# Side_Sensor.net
KiCad netlist of a schematic drawn in EasyEDA
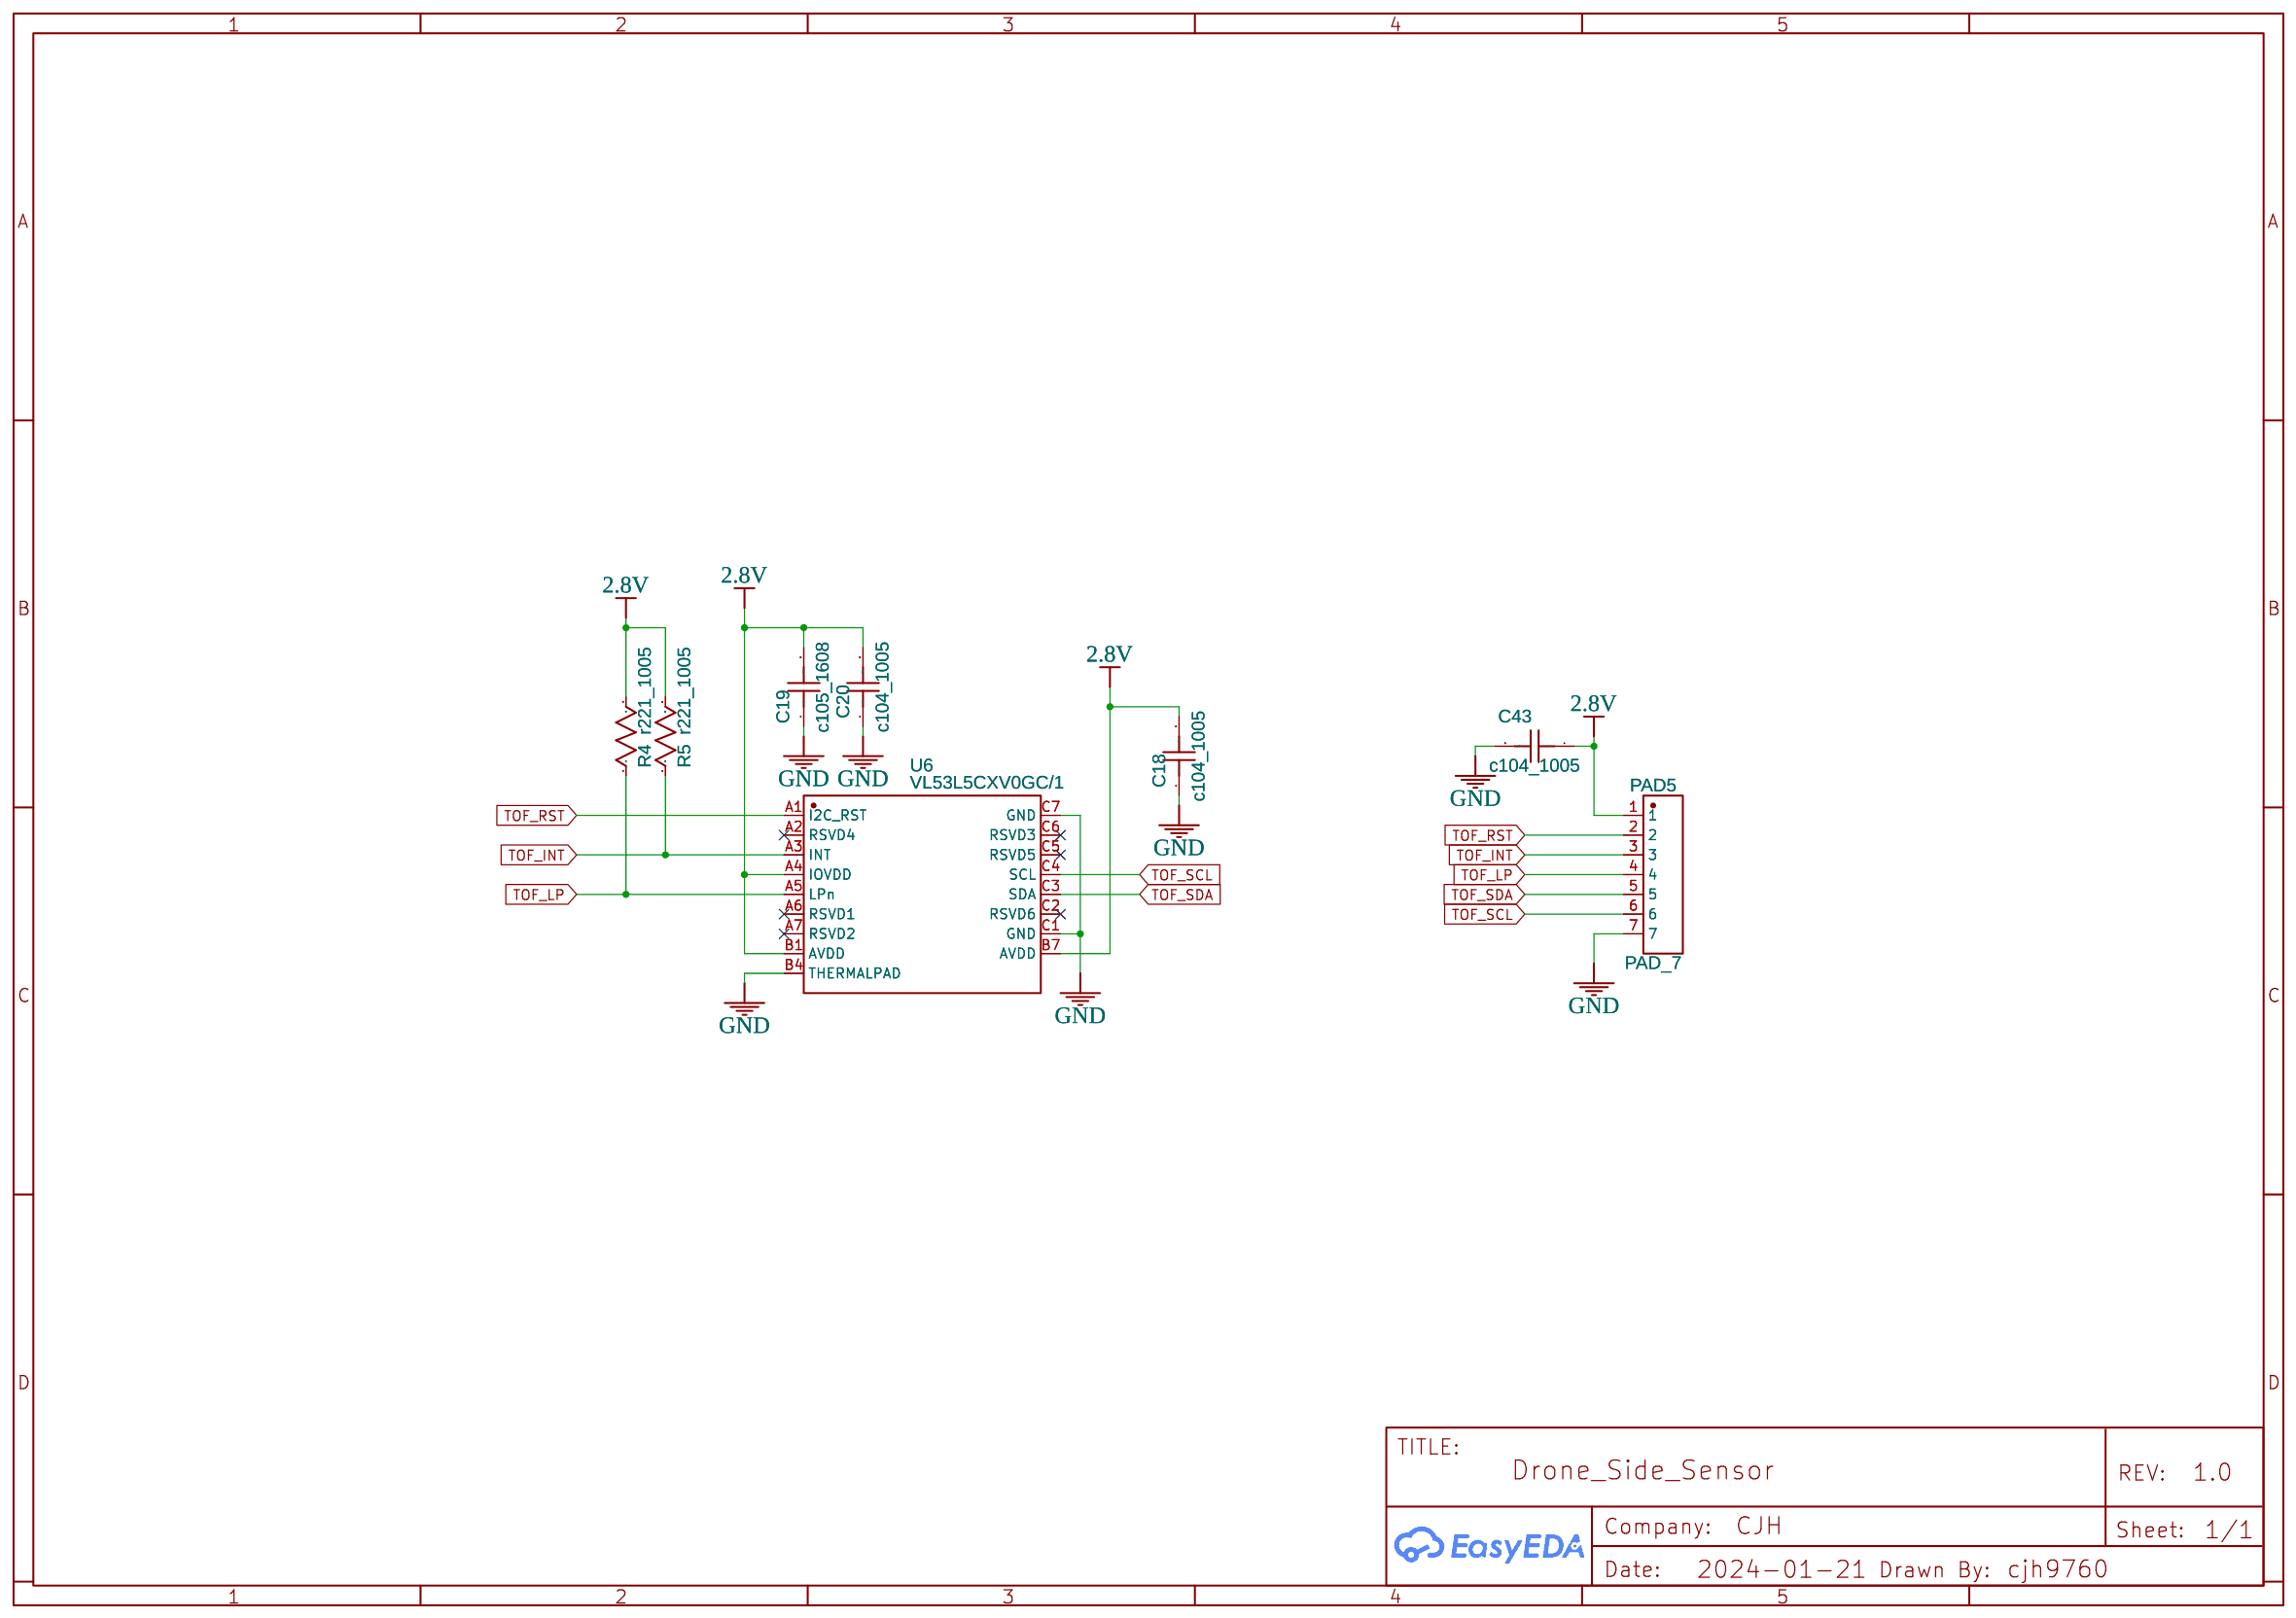
[diagram p0: schematic sheet]

(export (version "E")
  (design (tool "Eeschema 10.0.6"))
  (components
    (comp (ref "C18") (value "c104_1005") (libsource (lib "") (part "C_0402_US_1")))
    (comp (ref "C19") (value "c105_1608") (libsource (lib "") (part "C_0603_US")))
    (comp (ref "C20") (value "c104_1005") (libsource (lib "") (part "C_0402_US_1")))
    (comp (ref "C43") (value "c104_1005") (libsource (lib "") (part "C_0402_US")))
    (comp (ref "PAD5") (value "PAD_7") (libsource (lib "") (part "PAD_7")))
    (comp (ref "R4") (value "r221_1005") (libsource (lib "") (part "R_0402_US")))
    (comp (ref "R5") (value "r221_1005") (libsource (lib "") (part "R_0402_US")))
    (comp (ref "U6")
      (value "VL53L5CXV0GC/1")
      (fields (field (name "Manufacturer") "ST(意法半导体)"))
      (libsource (lib "") (part "VL53L5CXV0GC/1"))
    )
  )
  (nets
    (net (code "1") (name "2.8V") (class "Default")
      (node (ref "C18") (pin "2") (pinfunction "2_2") (pintype "unspecified"))
      (node (ref "C19") (pin "2") (pinfunction "2_2") (pintype "unspecified"))
      (node (ref "C20") (pin "2") (pinfunction "2_2") (pintype "unspecified"))
      (node (ref "C43") (pin "1") (pinfunction "1_1") (pintype "unspecified"))
      (node (ref "PAD5") (pin "1") (pinfunction "1_1") (pintype "unspecified"))
      (node (ref "R4") (pin "2") (pinfunction "2_2") (pintype "unspecified"))
      (node (ref "R5") (pin "2") (pinfunction "2_2") (pintype "unspecified"))
      (node (ref "U6") (pin "A4") (pinfunction "IOVDD_A4") (pintype "unspecified"))
      (node (ref "U6") (pin "B1") (pinfunction "AVDD_B1") (pintype "unspecified"))
      (node (ref "U6") (pin "B7") (pinfunction "AVDD_B7") (pintype "unspecified"))
    )
    (net (code "2") (name "GND") (class "Default")
      (node (ref "C18") (pin "1") (pinfunction "1_1") (pintype "unspecified"))
      (node (ref "C19") (pin "1") (pinfunction "1_1") (pintype "unspecified"))
      (node (ref "C20") (pin "1") (pinfunction "1_1") (pintype "unspecified"))
      (node (ref "C43") (pin "2") (pinfunction "2_2") (pintype "unspecified"))
      (node (ref "PAD5") (pin "7") (pinfunction "7_7") (pintype "unspecified"))
      (node (ref "U6") (pin "B4") (pinfunction "THERMALPAD_B4") (pintype "unspecified"))
      (node (ref "U6") (pin "C1") (pinfunction "GND_C1") (pintype "unspecified"))
      (node (ref "U6") (pin "C7") (pinfunction "GND_C7") (pintype "unspecified"))
    )
    (net (code "3") (name "TOF_INT") (class "Default")
      (node (ref "PAD5") (pin "3") (pinfunction "3_3") (pintype "unspecified"))
      (node (ref "R5") (pin "1") (pinfunction "1_1") (pintype "unspecified"))
      (node (ref "U6") (pin "A3") (pinfunction "INT_A3") (pintype "unspecified"))
    )
    (net (code "4") (name "TOF_LP") (class "Default")
      (node (ref "PAD5") (pin "4") (pinfunction "4_4") (pintype "unspecified"))
      (node (ref "R4") (pin "1") (pinfunction "1_1") (pintype "unspecified"))
      (node (ref "U6") (pin "A5") (pinfunction "LPn_A5") (pintype "unspecified"))
    )
    (net (code "5") (name "TOF_RST") (class "Default")
      (node (ref "PAD5") (pin "2") (pinfunction "2_2") (pintype "unspecified"))
      (node (ref "U6") (pin "A1") (pinfunction "I2C_RST_A1") (pintype "unspecified"))
    )
    (net (code "6") (name "TOF_SCL") (class "Default")
      (node (ref "PAD5") (pin "6") (pinfunction "6_6") (pintype "unspecified"))
      (node (ref "U6") (pin "C4") (pinfunction "SCL_C4") (pintype "unspecified"))
    )
    (net (code "7") (name "TOF_SDA") (class "Default")
      (node (ref "PAD5") (pin "5") (pinfunction "5_5") (pintype "unspecified"))
      (node (ref "U6") (pin "C3") (pinfunction "SDA_C3") (pintype "unspecified"))
    )
    (net (code "8") (name "unconnected-(U6-RSVD1-PadA6)") (class "Default")
      (node (ref "U6") (pin "A6") (pinfunction "RSVD1_A6") (pintype "unspecified+no_connect"))
    )
    (net (code "9") (name "unconnected-(U6-RSVD2-PadA7)") (class "Default")
      (node (ref "U6") (pin "A7") (pinfunction "RSVD2_A7") (pintype "unspecified+no_connect"))
    )
    (net (code "10") (name "unconnected-(U6-RSVD3-PadC6)") (class "Default")
      (node (ref "U6") (pin "C6") (pinfunction "RSVD3_C6") (pintype "unspecified+no_connect"))
    )
    (net (code "11") (name "unconnected-(U6-RSVD4-PadA2)") (class "Default")
      (node (ref "U6") (pin "A2") (pinfunction "RSVD4_A2") (pintype "unspecified+no_connect"))
    )
    (net (code "12") (name "unconnected-(U6-RSVD5-PadC5)") (class "Default")
      (node (ref "U6") (pin "C5") (pinfunction "RSVD5_C5") (pintype "unspecified+no_connect"))
    )
    (net (code "13") (name "unconnected-(U6-RSVD6-PadC2)") (class "Default")
      (node (ref "U6") (pin "C2") (pinfunction "RSVD6_C2") (pintype "unspecified+no_connect"))
    )
  )
)
